# Altium_Esp8266_2Relay_ICVietLife.net
KiCad netlist of a schematic drawn in Altium Designer
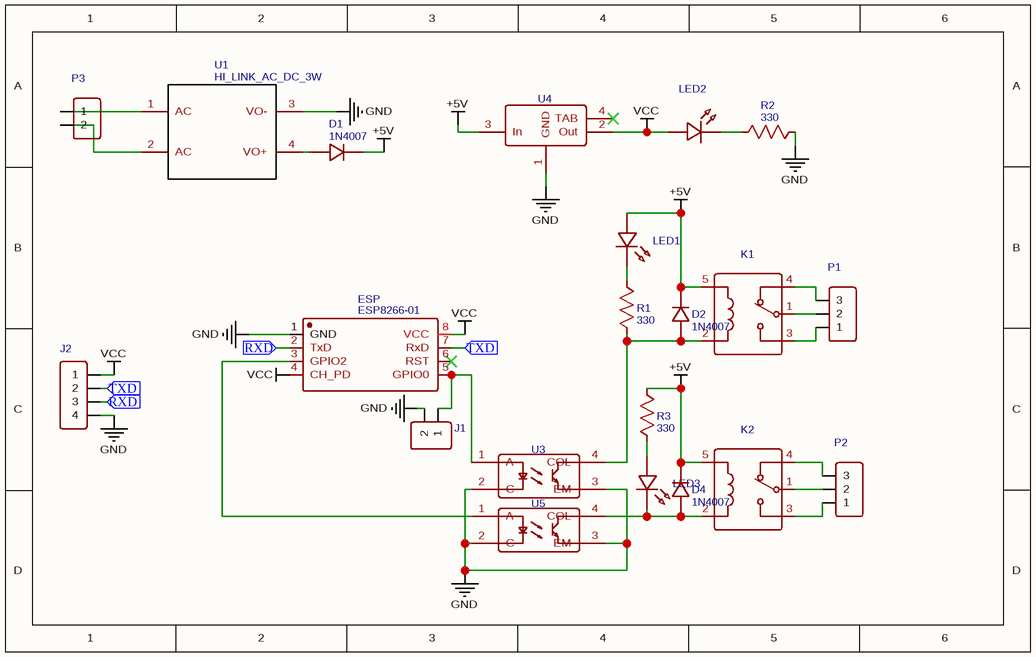
[diagram p0: Altium_Esp8266_2Relay_ICVietLife.schdoc]

(export (version "E")
  (design (tool "Eeschema 10.0.6"))
  (components
    (comp (ref "D1")
      (value "1N4007")
      (fields (field (name "BOM_SUPPLIER PART") "C106903") (field (name "CONTRIBUTOR") "LCEDA_Lib"))
      (libsource (lib "altium-import") (part "root_0_1N4007_"))
    )
    (comp (ref "D2")
      (value "1N4007")
      (fields (field (name "BOM_SUPPLIER PART") "C106903") (field (name "CONTRIBUTOR") "LCEDA_Lib"))
      (libsource (lib "altium-import") (part "root_1_1N4007_"))
    )
    (comp (ref "D4")
      (value "1N4007")
      (fields (field (name "BOM_SUPPLIER PART") "C106903") (field (name "CONTRIBUTOR") "LCEDA_Lib"))
      (libsource (lib "altium-import") (part "root_1_1N4007_"))
    )
    (comp (ref "ESP") (value "ESP8266-01") (libsource (lib "altium-import") (part "root_0_ESP8266-01_")))
    (comp (ref "J1")
      (value "HDR-M-2.54_1x2")
      (fields (field (name "BOM_SUPPLIER PART") "C124375") (field (name "CONTRIBUTOR") "LCEDA_Lib"))
      (libsource (lib "altium-import") (part "root_3_HDR-M-2.54_1x2_"))
    )
    (comp (ref "J2")
      (value "HDR-M-2.54_1x4")
      (fields (field (name "BOM_SUPPLIER PART") "C124378") (field (name "CONTRIBUTOR") "LCEDA_Lib"))
      (libsource (lib "altium-import") (part "root_0_HDR-M-2.54_1x4_"))
    )
    (comp (ref "K1")
      (value "RelayHT3F-12VDC-SHG")
      (fields (field (name "BOM_SUPPLIER PART") "C22022"))
      (libsource (lib "altium-import") (part "root_0_RelayHT3F-12VDC-SHG_"))
    )
    (comp (ref "K2")
      (value "RelayHT3F-12VDC-SHG")
      (fields (field (name "BOM_SUPPLIER PART") "C22022"))
      (libsource (lib "altium-import") (part "root_0_RelayHT3F-12VDC-SHG_"))
    )
    (comp (ref "LED1")
      (value "LED-TH-3mm_R")
      (fields
        (field (name "BOM_MANUFACTURER PART") "204-10SDRD/S530-A3-L")
        (field (name "BOM_SUPPLIER PART") "C84774")
        (field (name "CONTRIBUTOR") "LCEDA_Lib")
      )
      (libsource (lib "altium-import") (part "root_3_LED-TH-3mm_R_"))
    )
    (comp (ref "LED2")
      (value "LED-TH-3mm_R")
      (fields
        (field (name "BOM_MANUFACTURER PART") "204-10SDRD/S530-A3-L")
        (field (name "BOM_SUPPLIER PART") "C84774")
        (field (name "CONTRIBUTOR") "LCEDA_Lib")
      )
      (libsource (lib "altium-import") (part "root_0_LED-TH-3mm_R_"))
    )
    (comp (ref "LED3")
      (value "LED-TH-3mm_R")
      (fields
        (field (name "BOM_MANUFACTURER PART") "204-10SDRD/S530-A3-L")
        (field (name "BOM_SUPPLIER PART") "C84774")
        (field (name "CONTRIBUTOR") "LCEDA_Lib")
      )
      (libsource (lib "altium-import") (part "root_3_LED-TH-3mm_R_"))
    )
    (comp (ref "P1")
      (value "CONN-TH_3P-P5.00")
      (fields (field (name "CONTRIBUTOR") "LCEDA_Lib"))
      (libsource (lib "altium-import") (part "root_2_CONN-TH_3P-P5.00_"))
    )
    (comp (ref "P2")
      (value "CONN-TH_3P-P5.00")
      (fields (field (name "CONTRIBUTOR") "LCEDA_Lib"))
      (libsource (lib "altium-import") (part "root_2_CONN-TH_3P-P5.00_"))
    )
    (comp (ref "P3")
      (value "CONN-TH_2P-P5.00")
      (fields (field (name "CONTRIBUTOR") "LCEDA_Lib"))
      (libsource (lib "altium-import") (part "root_0_CONN-TH_2P-P5.00_"))
    )
    (comp (ref "R1")
      (value "330")
      (fields (field (name "CONTRIBUTOR") "LCEDA_Lib"))
      (libsource (lib "altium-import") (part "root_3_330_"))
    )
    (comp (ref "R2")
      (value "330")
      (fields (field (name "CONTRIBUTOR") "LCEDA_Lib"))
      (libsource (lib "altium-import") (part "root_0_330_"))
    )
    (comp (ref "R3")
      (value "330")
      (fields (field (name "CONTRIBUTOR") "LCEDA_Lib"))
      (libsource (lib "altium-import") (part "root_3_330_"))
    )
    (comp (ref "U1")
      (value "HI_LINK_AC_DC_3W")
      (fields
        (field (name "BOM_MANUFACTURER PART") "HI LINK")
        (field (name "CONTRIBUTOR") "sascha23095123423")
      )
      (libsource (lib "altium-import") (part "root_0_HI_LINK_AC_DC_3W_"))
    )
    (comp (ref "U3")
      (value "PC817C_C558562")
      (fields
        (field (name "BOM_SUPPLIER PART") "C558562")
        (field (name "BOM_MANUFACTURER PART") "PC817C")
        (field (name "CONTRIBUTOR") "LCSC")
      )
      (libsource (lib "altium-import") (part "root_0_PC817C_C558562_"))
    )
    (comp (ref "U4")
      (value "AMS1117-1.5_C166063")
      (fields
        (field (name "BOM_SUPPLIER PART") "C166063")
        (field (name "BOM_MANUFACTURER PART") "AMS1117-1.5")
        (field (name "CONTRIBUTOR") "LCSC")
      )
      (libsource (lib "altium-import") (part "root_0_AMS1117-1.5_C166063_"))
    )
    (comp (ref "U5")
      (value "PC817C_C558562")
      (fields
        (field (name "BOM_SUPPLIER PART") "C558562")
        (field (name "BOM_MANUFACTURER PART") "PC817C")
        (field (name "CONTRIBUTOR") "LCSC")
      )
      (libsource (lib "altium-import") (part "root_0_PC817C_C558562_"))
    )
  )
  (nets
    (net (code "1") (name "+5V") (class "Default")
      (node (ref "D1") (pin "1") (pinfunction "1_1") (pintype "passive"))
      (node (ref "D2") (pin "1") (pinfunction "1_1") (pintype "passive"))
      (node (ref "D4") (pin "1") (pinfunction "1_1") (pintype "passive"))
      (node (ref "K1") (pin "5") (pinfunction "5_5") (pintype "passive"))
      (node (ref "K2") (pin "5") (pinfunction "5_5") (pintype "passive"))
      (node (ref "LED1") (pin "1") (pinfunction "1_1") (pintype "passive"))
      (node (ref "R3") (pin "1") (pinfunction "1_1") (pintype "passive"))
      (node (ref "U4") (pin "3") (pinfunction "In_3") (pintype "passive"))
    )
    (net (code "2") (name "/RXD") (class "Default")
      (node (ref "ESP") (pin "2") (pinfunction "TxD_2") (pintype "passive"))
      (node (ref "J2") (pin "3") (pinfunction "3_3") (pintype "passive"))
    )
    (net (code "3") (name "/TXD") (class "Default")
      (node (ref "ESP") (pin "7") (pinfunction "RxD_7") (pintype "passive"))
      (node (ref "J2") (pin "2") (pinfunction "2_2") (pintype "passive"))
    )
    (net (code "4") (name "GND") (class "Default")
      (node (ref "ESP") (pin "1") (pinfunction "GND_1") (pintype "passive"))
      (node (ref "J1") (pin "2") (pinfunction "2_2") (pintype "passive"))
      (node (ref "J2") (pin "4") (pinfunction "4_4") (pintype "passive"))
      (node (ref "R2") (pin "2") (pinfunction "2_2") (pintype "passive"))
      (node (ref "U1") (pin "3") (pinfunction "VO-_3") (pintype "passive"))
      (node (ref "U3") (pin "2") (pinfunction "C_2") (pintype "passive"))
      (node (ref "U3") (pin "3") (pinfunction "EM_3") (pintype "passive"))
      (node (ref "U4") (pin "1") (pinfunction "GND_1") (pintype "passive"))
      (node (ref "U5") (pin "2") (pinfunction "C_2") (pintype "passive"))
      (node (ref "U5") (pin "3") (pinfunction "EM_3") (pintype "passive"))
    )
    (net (code "5") (name "Net-(ESP-GPIO0)") (class "Default")
      (node (ref "ESP") (pin "5") (pinfunction "GPIO0_5") (pintype "passive"))
      (node (ref "J1") (pin "1") (pinfunction "1_1") (pintype "passive"))
      (node (ref "U3") (pin "1") (pinfunction "A_1") (pintype "passive"))
    )
    (net (code "6") (name "Net-(ESP-GPIO2)") (class "Default")
      (node (ref "ESP") (pin "3") (pinfunction "GPIO2_3") (pintype "passive"))
      (node (ref "U5") (pin "1") (pinfunction "A_1") (pintype "passive"))
    )
    (net (code "7") (name "Net-(K1-Pad1)") (class "Default")
      (node (ref "K1") (pin "1") (pinfunction "1_1") (pintype "passive"))
      (node (ref "P1") (pin "2") (pinfunction "2_2") (pintype "passive"))
    )
    (net (code "8") (name "Net-(K1-Pad3)") (class "Default")
      (node (ref "K1") (pin "3") (pinfunction "3_3") (pintype "passive"))
      (node (ref "P1") (pin "1") (pinfunction "1_1") (pintype "passive"))
    )
    (net (code "9") (name "Net-(K1-Pad4)") (class "Default")
      (node (ref "K1") (pin "4") (pinfunction "4_4") (pintype "passive"))
      (node (ref "P1") (pin "3") (pinfunction "3_3") (pintype "passive"))
    )
    (net (code "10") (name "Net-(K2-Pad1)") (class "Default")
      (node (ref "K2") (pin "1") (pinfunction "1_1") (pintype "passive"))
      (node (ref "P2") (pin "2") (pinfunction "2_2") (pintype "passive"))
    )
    (net (code "11") (name "Net-(K2-Pad3)") (class "Default")
      (node (ref "K2") (pin "3") (pinfunction "3_3") (pintype "passive"))
      (node (ref "P2") (pin "1") (pinfunction "1_1") (pintype "passive"))
    )
    (net (code "12") (name "Net-(K2-Pad4)") (class "Default")
      (node (ref "K2") (pin "4") (pinfunction "4_4") (pintype "passive"))
      (node (ref "P2") (pin "3") (pinfunction "3_3") (pintype "passive"))
    )
    (net (code "13") (name "Net-(LED1-Pad2)") (class "Default")
      (node (ref "LED1") (pin "2") (pinfunction "2_2") (pintype "passive"))
      (node (ref "R1") (pin "1") (pinfunction "1_1") (pintype "passive"))
    )
    (net (code "14") (name "Net-(LED2-Pad2)") (class "Default")
      (node (ref "LED2") (pin "2") (pinfunction "2_2") (pintype "passive"))
      (node (ref "R2") (pin "1") (pinfunction "1_1") (pintype "passive"))
    )
    (net (code "15") (name "Net-(LED3-Pad1)") (class "Default")
      (node (ref "LED3") (pin "1") (pinfunction "1_1") (pintype "passive"))
      (node (ref "R3") (pin "2") (pinfunction "2_2") (pintype "passive"))
    )
    (net (code "16") (name "Net-(P3-Pad1)") (class "Default")
      (node (ref "P3") (pin "1") (pinfunction "1_1") (pintype "passive"))
      (node (ref "U1") (pin "1") (pinfunction "AC_1") (pintype "passive"))
    )
    (net (code "17") (name "Net-(P3-Pad2)") (class "Default")
      (node (ref "P3") (pin "2") (pinfunction "2_2") (pintype "passive"))
      (node (ref "U1") (pin "2") (pinfunction "AC_2") (pintype "passive"))
    )
    (net (code "18") (name "Net-(U1-VO+)") (class "Default")
      (node (ref "D1") (pin "2") (pinfunction "2_2") (pintype "passive"))
      (node (ref "U1") (pin "4") (pinfunction "VO+_4") (pintype "passive"))
    )
    (net (code "19") (name "Net-(U3-COL)") (class "Default")
      (node (ref "D2") (pin "2") (pinfunction "2_2") (pintype "passive"))
      (node (ref "K1") (pin "2") (pinfunction "2_2") (pintype "passive"))
      (node (ref "R1") (pin "2") (pinfunction "2_2") (pintype "passive"))
      (node (ref "U3") (pin "4") (pinfunction "COL_4") (pintype "passive"))
    )
    (net (code "20") (name "Net-(U5-COL)") (class "Default")
      (node (ref "D4") (pin "2") (pinfunction "2_2") (pintype "passive"))
      (node (ref "K2") (pin "2") (pinfunction "2_2") (pintype "passive"))
      (node (ref "LED3") (pin "2") (pinfunction "2_2") (pintype "passive"))
      (node (ref "U5") (pin "4") (pinfunction "COL_4") (pintype "passive"))
    )
    (net (code "21") (name "VCC") (class "Default")
      (node (ref "ESP") (pin "4") (pinfunction "CH_PD_4") (pintype "passive"))
      (node (ref "ESP") (pin "8") (pinfunction "VCC_8") (pintype "passive"))
      (node (ref "J2") (pin "1") (pinfunction "1_1") (pintype "passive"))
      (node (ref "LED2") (pin "1") (pinfunction "1_1") (pintype "passive"))
      (node (ref "U4") (pin "2") (pinfunction "Out_2") (pintype "passive"))
    )
    (net (code "22") (name "unconnected-(ESP-RST-Pad6)") (class "Default")
      (node (ref "ESP") (pin "6") (pinfunction "RST_6") (pintype "passive+no_connect"))
    )
    (net (code "23") (name "unconnected-(U4-TAB-Pad4)") (class "Default")
      (node (ref "U4") (pin "4") (pinfunction "TAB_4") (pintype "passive+no_connect"))
    )
  )
)
